# Control_Board.net
KiCad netlist of a schematic drawn in Altium Designer
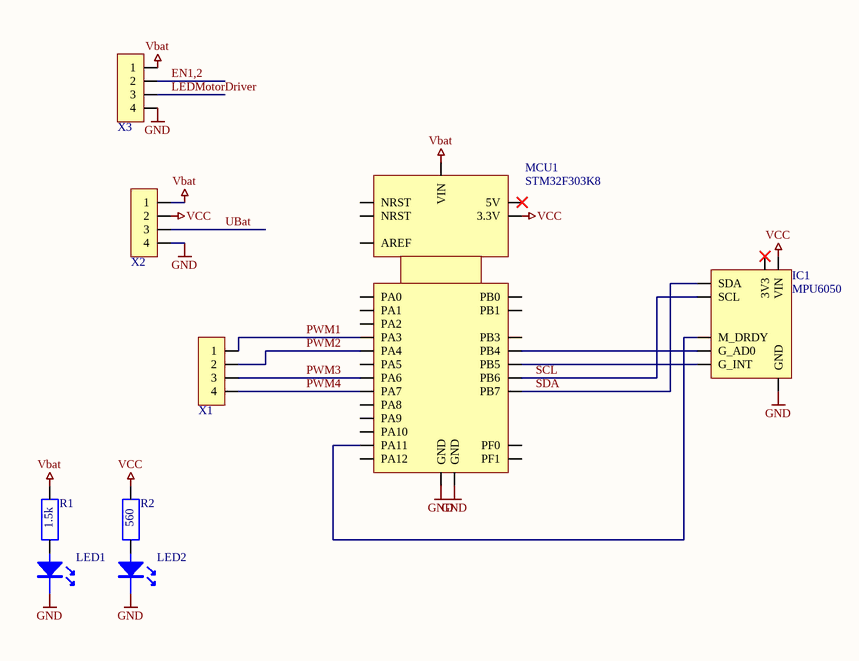
[diagram p0: Control Board.SchDoc]

(export (version "E")
  (design (tool "Eeschema 10.0.6"))
  (components
    (comp (ref "IC1")
      (value "MPU6050")
      (footprint "MPU6050-Board")
      (description "MPU6050 Sensor Board")
      (libsource (lib "Library") (part "MPU6050 Board"))
    )
    (comp (ref "LED1")
      (value "APT3216CGCK")
      (footprint "LED_3216_GREEN")
      (description "LED SMD green APT3216CGCK")
      (fields (field (name "MANUFACTURER") "Kingbright") (field (name "PART NUMBER") "604-APT3216CGCK"))
      (libsource (lib "Library Smarthome Box") (part "LED"))
    )
    (comp (ref "LED2")
      (value "APT3216CGCK")
      (footprint "LED_3216_GREEN")
      (description "LED SMD green APT3216CGCK")
      (fields (field (name "MANUFACTURER") "Kingbright") (field (name "PART NUMBER") "604-APT3216CGCK"))
      (libsource (lib "Library Smarthome Box") (part "LED"))
    )
    (comp (ref "MCU1")
      (value "STM32F303K8")
      (footprint "Nucleo STM32F303K8")
      (libsource (lib "Library") (part "Nucleo STM32F303K8"))
    )
    (comp (ref "R1")
      (value "Chip Resistor 10k, 0805, 1%")
      (footprint "0805_R")
      (description "Resistor 10k 0.125W 0805")
      (fields
        (field (name "MANUFACTURER") "Vishay")
        (field (name "PART NUMBER") "CRCW080510K0FKEAC")
        (field (name "COMMENT_1") "1.5k")
      )
      (libsource (lib "Library Smarthome Box") (part "RESISTOR"))
    )
    (comp (ref "R2")
      (value "Chip Resistor 10k, 0805, 1%")
      (footprint "0805_R")
      (description "Resistor 10k 0.125W 0805")
      (fields
        (field (name "MANUFACTURER") "Vishay")
        (field (name "PART NUMBER") "CRCW080510K0FKEAC")
        (field (name "COMMENT_1") "560")
      )
      (libsource (lib "Library Smarthome Box") (part "RESISTOR"))
    )
    (comp (ref "X1")
      (value "Pin Header 4x1 2.54mm")
      (footprint "PTSM 0,5 4-2,5-H SMD")
      (description "PTSM 4 Pol")
      (fields (field (name "MANUFACTURER") "Phoenix Contacdt") (field (name "PART NUMBER") "1814650"))
      (libsource (lib "Library") (part "PTSM 0,5/ 4-2,5-H SMD"))
    )
    (comp (ref "X2")
      (value "Pin Header 4x1 2.54mm")
      (footprint "PTSM 0,5 4-2,5-H SMD")
      (description "PTSM 4 Pol")
      (fields (field (name "MANUFACTURER") "Phoenix Contacdt") (field (name "PART NUMBER") "1814650"))
      (libsource (lib "Library") (part "PTSM 0,5/ 4-2,5-H SMD"))
    )
    (comp (ref "X3")
      (value "Pin Header 4x1 2.54mm")
      (footprint "PTSM 0,5 4-2,5-H SMD")
      (description "PTSM 4 Pol")
      (fields (field (name "MANUFACTURER") "Phoenix Contacdt") (field (name "PART NUMBER") "1814650"))
      (libsource (lib "Library") (part "PTSM 0,5/ 4-2,5-H SMD"))
    )
  )
  (nets
    (net (code "1") (name "/EN1,2") (class "Default")
      (node (ref "X3") (pin "2") (pinfunction "2_2") (pintype "passive"))
    )
    (net (code "2") (name "/LEDMotorDriver") (class "Default")
      (node (ref "X3") (pin "3") (pinfunction "3_3") (pintype "passive"))
    )
    (net (code "3") (name "/PWM1") (class "Default")
      (node (ref "MCU1") (pin "25") (pinfunction "PA3_25") (pintype "passive"))
      (node (ref "X1") (pin "1") (pinfunction "1_1") (pintype "passive"))
    )
    (net (code "4") (name "/PWM2") (class "Default")
      (node (ref "MCU1") (pin "24") (pinfunction "PA4_24") (pintype "passive"))
      (node (ref "X1") (pin "2") (pinfunction "2_2") (pintype "passive"))
    )
    (net (code "5") (name "/PWM3") (class "Default")
      (node (ref "MCU1") (pin "22") (pinfunction "PA6_22") (pintype "passive"))
      (node (ref "X1") (pin "3") (pinfunction "3_3") (pintype "passive"))
    )
    (net (code "6") (name "/PWM4") (class "Default")
      (node (ref "MCU1") (pin "21") (pinfunction "PA7_21") (pintype "passive"))
      (node (ref "X1") (pin "4") (pinfunction "4_4") (pintype "passive"))
    )
    (net (code "7") (name "/SCL") (class "Default")
      (node (ref "IC1") (pin "4") (pinfunction "SCL_4") (pintype "passive"))
      (node (ref "MCU1") (pin "8") (pinfunction "PB6_8") (pintype "passive"))
    )
    (net (code "8") (name "/SDA") (class "Default")
      (node (ref "IC1") (pin "5") (pinfunction "SDA_5") (pintype "passive"))
      (node (ref "MCU1") (pin "7") (pinfunction "PB7_7") (pintype "passive"))
    )
    (net (code "9") (name "/UBat") (class "Default")
      (node (ref "X2") (pin "3") (pinfunction "3_3") (pintype "passive"))
    )
    (net (code "10") (name "GND") (class "Default")
      (node (ref "IC1") (pin "3") (pinfunction "GND_3") (pintype "passive"))
      (node (ref "LED1") (pin "K") (pinfunction "2_K") (pintype "passive"))
      (node (ref "LED2") (pin "K") (pinfunction "2_K") (pintype "passive"))
      (node (ref "MCU1") (pin "17") (pinfunction "GND_17") (pintype "passive"))
      (node (ref "MCU1") (pin "4") (pinfunction "GND_4") (pintype "passive"))
      (node (ref "X2") (pin "4") (pinfunction "4_4") (pintype "passive"))
      (node (ref "X3") (pin "4") (pinfunction "4_4") (pintype "passive"))
    )
    (net (code "11") (name "Net-(IC1-G_AD0)") (class "Default")
      (node (ref "IC1") (pin "7") (pinfunction "G_AD0_7") (pintype "passive"))
      (node (ref "MCU1") (pin "15") (pinfunction "PB4_15") (pintype "passive"))
    )
    (net (code "12") (name "Net-(IC1-G_INT)") (class "Default")
      (node (ref "IC1") (pin "8") (pinfunction "G_INT_8") (pintype "passive"))
      (node (ref "MCU1") (pin "14") (pinfunction "PB5_14") (pintype "passive"))
    )
    (net (code "13") (name "Net-(IC1-M_DRDY)") (class "Default")
      (node (ref "IC1") (pin "6") (pinfunction "M_DRDY_6") (pintype "passive"))
      (node (ref "MCU1") (pin "13") (pinfunction "PA11_13") (pintype "passive"))
    )
    (net (code "14") (name "Net-(LED1-1)") (class "Default")
      (node (ref "LED1") (pin "A") (pinfunction "1_A") (pintype "passive"))
      (node (ref "R1") (pin "1") (pintype "passive"))
    )
    (net (code "15") (name "Net-(LED2-1)") (class "Default")
      (node (ref "LED2") (pin "A") (pinfunction "1_A") (pintype "passive"))
      (node (ref "R2") (pin "1") (pintype "passive"))
    )
    (net (code "16") (name "VCC") (class "Default")
      (node (ref "IC1") (pin "1") (pinfunction "VIN_1") (pintype "passive"))
      (node (ref "MCU1") (pin "29") (pinfunction "3.3V_29") (pintype "passive"))
      (node (ref "R2") (pin "2") (pintype "passive"))
      (node (ref "X2") (pin "2") (pinfunction "2_2") (pintype "passive"))
    )
    (net (code "17") (name "Vbat") (class "Default")
      (node (ref "MCU1") (pin "16") (pinfunction "VIN_16") (pintype "passive"))
      (node (ref "R1") (pin "2") (pintype "passive"))
      (node (ref "X2") (pin "1") (pinfunction "1_1") (pintype "passive"))
      (node (ref "X3") (pin "1") (pinfunction "1_1") (pintype "passive"))
    )
    (net (code "18") (name "unconnected-(IC1-3V3-Pad2)") (class "Default")
      (node (ref "IC1") (pin "2") (pinfunction "3V3_2") (pintype "passive+no_connect"))
    )
    (net (code "19") (name "unconnected-(MCU1-5V-Pad19)") (class "Default")
      (node (ref "MCU1") (pin "19") (pinfunction "5V_19") (pintype "passive+no_connect"))
    )
    (net (code "20") (name "unconnected-(MCU1-AREF-Pad28)") (class "Default")
      (node (ref "MCU1") (pin "28") (pinfunction "AREF_28") (pintype "passive"))
    )
    (net (code "21") (name "unconnected-(MCU1-NRST-Pad3)") (class "Default")
      (node (ref "MCU1") (pin "3") (pinfunction "NRST_3") (pintype "passive"))
    )
    (net (code "22") (name "unconnected-(MCU1-NRST-Pad18)") (class "Default")
      (node (ref "MCU1") (pin "18") (pinfunction "NRST_18") (pintype "passive"))
    )
    (net (code "23") (name "unconnected-(MCU1-PA0-Pad27)") (class "Default")
      (node (ref "MCU1") (pin "27") (pinfunction "PA0_27") (pintype "passive"))
    )
    (net (code "24") (name "unconnected-(MCU1-PA1-Pad26)") (class "Default")
      (node (ref "MCU1") (pin "26") (pinfunction "PA1_26") (pintype "passive"))
    )
    (net (code "25") (name "unconnected-(MCU1-PA2-Pad20)") (class "Default")
      (node (ref "MCU1") (pin "20") (pinfunction "PA2_20") (pintype "passive"))
    )
    (net (code "26") (name "unconnected-(MCU1-PA5-Pad23)") (class "Default")
      (node (ref "MCU1") (pin "23") (pinfunction "PA5_23") (pintype "passive"))
    )
    (net (code "27") (name "unconnected-(MCU1-PA8-Pad12)") (class "Default")
      (node (ref "MCU1") (pin "12") (pinfunction "PA8_12") (pintype "passive"))
    )
    (net (code "28") (name "unconnected-(MCU1-PA9-Pad1)") (class "Default")
      (node (ref "MCU1") (pin "1") (pinfunction "PA9_1") (pintype "passive"))
    )
    (net (code "29") (name "unconnected-(MCU1-PA10-Pad2)") (class "Default")
      (node (ref "MCU1") (pin "2") (pinfunction "PA10_2") (pintype "passive"))
    )
    (net (code "30") (name "unconnected-(MCU1-PA12-Pad5)") (class "Default")
      (node (ref "MCU1") (pin "5") (pinfunction "PA12_5") (pintype "passive"))
    )
    (net (code "31") (name "unconnected-(MCU1-PB0-Pad6)") (class "Default")
      (node (ref "MCU1") (pin "6") (pinfunction "PB0_6") (pintype "passive"))
    )
    (net (code "32") (name "unconnected-(MCU1-PB1-Pad9)") (class "Default")
      (node (ref "MCU1") (pin "9") (pinfunction "PB1_9") (pintype "passive"))
    )
    (net (code "33") (name "unconnected-(MCU1-PB3-Pad30)") (class "Default")
      (node (ref "MCU1") (pin "30") (pinfunction "PB3_30") (pintype "passive"))
    )
    (net (code "34") (name "unconnected-(MCU1-PF0-Pad10)") (class "Default")
      (node (ref "MCU1") (pin "10") (pinfunction "PF0_10") (pintype "passive"))
    )
    (net (code "35") (name "unconnected-(MCU1-PF1-Pad11)") (class "Default")
      (node (ref "MCU1") (pin "11") (pinfunction "PF1_11") (pintype "passive"))
    )
  )
)
